# Group14ReceiverSchematic.net
KiCad netlist of a schematic drawn in Altium Designer
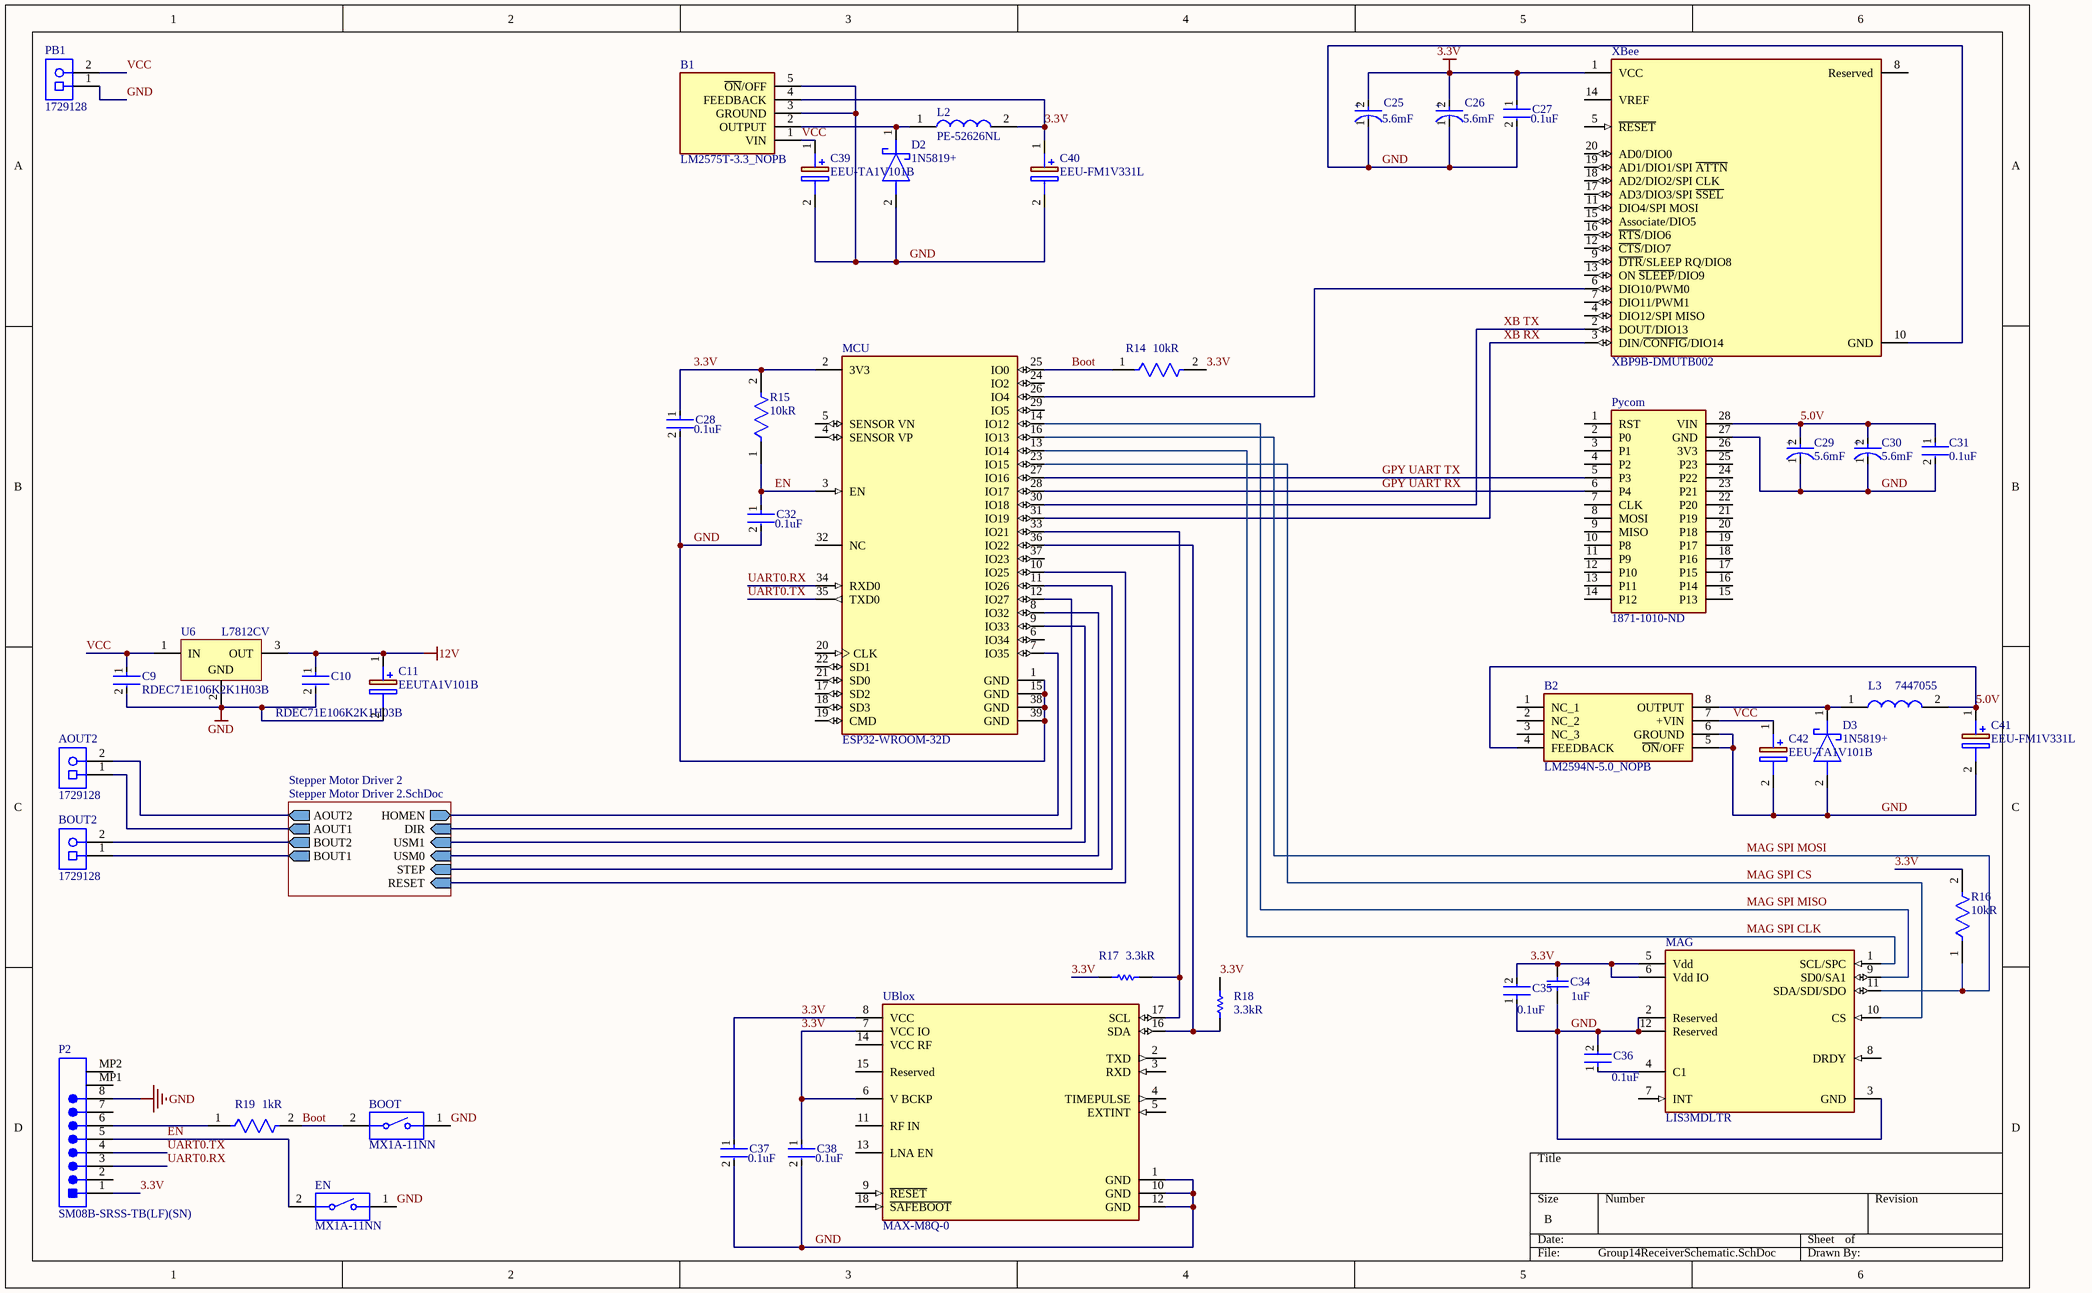
[diagram p0: Group14ReceiverSchematic.SchDoc]

(export (version "E")
  (design (tool "Eeschema 10.0.6"))
  (components
    (comp (ref "AOUT2")
      (value "1729128")
      (footprint "PHOE-1729128-2_V")
      (description "PCB Terminal Block, 13.5 A, 400 V, 2-Pin THD, RoHS, Bulk")
      (fields (field (name "MANUFACTURER") "Phoenix Contact"))
      (libsource (lib "Altium Content Vault") (part "CN-2P-F-R2"))
    )
    (comp (ref "B1")
      (value "LM2575T-3.3_NOPB")
      (footprint "SamacSys:LM2575T33NOPB")
      (description "Integrated Circuit")
      (fields
        (field (name "MANUFACTURER_PART_NUMBER") "LM2575T-3.3/NOPB")
        (field (name "MOUSER PART NUMBER") "926-LM2575T-33/NOPB")
      )
      (libsource (lib "SamacSys") (part "LM2575T-3.3_NOPB"))
    )
    (comp (ref "B2")
      (value "LM2594N-5.0_NOPB")
      (footprint "SamacSys:DIP794W53P254L959H508Q8N")
      (description "Integrated Circuit")
      (fields
        (field (name "MANUFACTURER_PART_NUMBER") "LM2594N-5.0/NOPB")
        (field (name "MOUSER PART NUMBER") "926-LM2594N-5.0/NOPB")
      )
      (libsource (lib "*") (part "LM2594N-5.0_NOPB"))
    )
    (comp (ref "BOOT")
      (value "MX1A-11NN")
      (footprint "CHRY-MX1A-11NN_V")
      (description "Keymodule MX, SPST, IP40, 12 V Max, 10 mA Max, -10 to 70 degC, 2-Pin THD, RoHS, Bulk")
      (fields (field (name "PART NO") "MX1A11NN") (field (name "MANUFACTURER") "Cherry"))
      (libsource (lib "Altium Content Vault") (part "KEYSW-SPST-2"))
    )
    (comp (ref "BOUT2")
      (value "1729128")
      (footprint "PHOE-1729128-2_V")
      (description "PCB Terminal Block, 13.5 A, 400 V, 2-Pin THD, RoHS, Bulk")
      (fields (field (name "MANUFACTURER") "Phoenix Contact"))
      (libsource (lib "Altium Content Vault") (part "CN-2P-F-R2"))
    )
    (comp (ref "C9")
      (value "RDEC71E106K2K1H03B")
      (footprint "FP-RDE2M1-MFG")
      (description "Ceramic Capacitor 10uF ±10% 25V X7S Radial")
      (fields (field (name "TOLERANCE") "10%"))
      (libsource (lib "Altium Content Vault") (part "b4654b650e69147ec39a6b967a45e02"))
    )
    (comp (ref "C10")
      (value "RDEC71E106K2K1H03B")
      (footprint "FP-RDE2M1-MFG")
      (description "Ceramic Capacitor 10uF ±10% 25V X7S Radial")
      (fields (field (name "TOLERANCE") "10%"))
      (libsource (lib "Altium Content Vault") (part "b4654b650e69147ec39a6b967a45e02"))
    )
    (comp (ref "C11")
      (value "EEUTA1V101B")
      (footprint "SamacSys:CAPPRD500W65D1000H1350")
      (description "Capacitor Polarised")
      (libsource (lib "*") (part "EEUTA1V101B"))
    )
    (comp (ref "C25")
      (value "EEUFM0J562S")
      (footprint "FP-RAD-TH-D_16_0_5-L_20_2-MFG")
      (description "Aluminum Electrolytic Capacitors (Radial Lead Type) 5600uF ±20% 6.3V")
      (fields
        (field (name "TOLERANCE") "20%")
        (field (name "VOLTAGE") "6.3V")
        (field (name "CAPACITANCE") "5.6mF")
      )
      (libsource (lib "Altium Content Vault") (part "203bc49f2ac43e59fd269a8c329ed05"))
    )
    (comp (ref "C26")
      (value "EEUFM0J562S")
      (footprint "FP-RAD-TH-D_16_0_5-L_20_2-MFG")
      (description "Aluminum Electrolytic Capacitors (Radial Lead Type) 5600uF ±20% 6.3V")
      (fields
        (field (name "TOLERANCE") "20%")
        (field (name "VOLTAGE") "6.3V")
        (field (name "CAPACITANCE") "5.6mF")
      )
      (libsource (lib "Altium Content Vault") (part "203bc49f2ac43e59fd269a8c329ed05"))
    )
    (comp (ref "C27")
      (value "RCER71E104K0K1H03B")
      (footprint "FP-RCE0K1-MFG")
      (description "Cap Ceramic 100nF 25V X7R ±10% Radial 5mm +125°C Automotive Bulk")
      (fields (field (name "CAPACITANCE") "0.1uF"))
      (libsource (lib "Altium Content Vault") (part "b4654b650e69147ec39a6b967a45e02"))
    )
    (comp (ref "C28")
      (value "RCER71E104K0K1H03B")
      (footprint "FP-RCE0K1-MFG")
      (description "Cap Ceramic 100nF 25V X7R ±10% Radial 5mm +125°C Automotive Bulk")
      (fields (field (name "CAPACITANCE") "0.1uF"))
      (libsource (lib "Altium Content Vault") (part "b4654b650e69147ec39a6b967a45e02"))
    )
    (comp (ref "C29")
      (value "EEUFM0J562S")
      (footprint "FP-RAD-TH-D_16_0_5-L_20_2-MFG")
      (description "Aluminum Electrolytic Capacitors (Radial Lead Type) 5600uF ±20% 6.3V")
      (fields
        (field (name "TOLERANCE") "20%")
        (field (name "VOLTAGE") "6.3V")
        (field (name "CAPACITANCE") "5.6mF")
      )
      (libsource (lib "Altium Content Vault") (part "203bc49f2ac43e59fd269a8c329ed05"))
    )
    (comp (ref "C30")
      (value "EEUFM0J562S")
      (footprint "FP-RAD-TH-D_16_0_5-L_20_2-MFG")
      (description "Aluminum Electrolytic Capacitors (Radial Lead Type) 5600uF ±20% 6.3V")
      (fields
        (field (name "TOLERANCE") "20%")
        (field (name "VOLTAGE") "6.3V")
        (field (name "CAPACITANCE") "5.6mF")
      )
      (libsource (lib "Altium Content Vault") (part "203bc49f2ac43e59fd269a8c329ed05"))
    )
    (comp (ref "C31")
      (value "RCER71E104K0K1H03B")
      (footprint "FP-RCE0K1-MFG")
      (description "Cap Ceramic 100nF 25V X7R ±10% Radial 5mm +125°C Automotive Bulk")
      (fields (field (name "CAPACITANCE") "0.1uF"))
      (libsource (lib "Altium Content Vault") (part "b4654b650e69147ec39a6b967a45e02"))
    )
    (comp (ref "C32")
      (value "RCER71E104K0K1H03B")
      (footprint "FP-RCE0K1-MFG")
      (description "Cap Ceramic 100nF 25V X7R ±10% Radial 5mm +125°C Automotive Bulk")
      (fields (field (name "CAPACITANCE") "0.1uF"))
      (libsource (lib "Altium Content Vault") (part "b4654b650e69147ec39a6b967a45e02"))
    )
    (comp (ref "C34")
      (value "0805YC105JAT2A")
      (footprint "CAPC2013X140X50ML20T25")
      (fields (field (name "MANUFACTURER") "AVX Interconnect / Elco") (field (name "CAPACITANCE") "1uF"))
      (libsource (lib "Altium Content Vault") (part "CAP"))
    )
    (comp (ref "C35")
      (value "RCER71E104K0K1H03B")
      (footprint "FP-RCE0K1-MFG")
      (description "Cap Ceramic 100nF 25V X7R ±10% Radial 5mm +125°C Automotive Bulk")
      (fields (field (name "CAPACITANCE") "0.1uF"))
      (libsource (lib "Altium Content Vault") (part "b4654b650e69147ec39a6b967a45e02"))
    )
    (comp (ref "C36")
      (value "RCER71E104K0K1H03B")
      (footprint "FP-RCE0K1-MFG")
      (description "Cap Ceramic 100nF 25V X7R ±10% Radial 5mm +125°C Automotive Bulk")
      (fields (field (name "CAPACITANCE") "0.1uF"))
      (libsource (lib "Altium Content Vault") (part "b4654b650e69147ec39a6b967a45e02"))
    )
    (comp (ref "C37")
      (value "RCER71E104K0K1H03B")
      (footprint "FP-RCE0K1-MFG")
      (description "Cap Ceramic 100nF 25V X7R ±10% Radial 5mm +125°C Automotive Bulk")
      (fields (field (name "CAPACITANCE") "0.1uF"))
      (libsource (lib "Altium Content Vault") (part "b4654b650e69147ec39a6b967a45e02"))
    )
    (comp (ref "C38")
      (value "RCER71E104K0K1H03B")
      (footprint "FP-RCE0K1-MFG")
      (description "Cap Ceramic 100nF 25V X7R ±10% Radial 5mm +125°C Automotive Bulk")
      (fields (field (name "CAPACITANCE") "0.1uF"))
      (libsource (lib "Altium Content Vault") (part "b4654b650e69147ec39a6b967a45e02"))
    )
    (comp (ref "C39")
      (value "EEU-TA1V101B")
      (footprint "SamacSys:CAPPRD500W65D1000H1350")
      (description "Capacitor Polarised")
      (fields (field (name "MOUSER PART NUMBER") "667-EEU-TA1V101B"))
      (libsource (lib "*") (part "EEU-TA1V101B"))
    )
    (comp (ref "C40")
      (value "EEU-FM1V331L")
      (footprint "SamacSys:CAPPRD350W60D800H2200")
      (description "Capacitor Polarised")
      (fields (field (name "MOUSER PART NUMBER") "667-EEU-FM1V331L"))
      (libsource (lib "*") (part "EEU-FM1V331L"))
    )
    (comp (ref "C41")
      (value "EEU-FM1V331L")
      (footprint "SamacSys:CAPPRD350W60D800H2200")
      (description "Capacitor Polarised")
      (fields (field (name "MOUSER PART NUMBER") "667-EEU-FM1V331L"))
      (libsource (lib "*") (part "EEU-FM1V331L"))
    )
    (comp (ref "C42")
      (value "EEU-TA1V101B")
      (footprint "SamacSys:CAPPRD500W65D1000H1350")
      (description "Capacitor Polarised")
      (fields (field (name "MOUSER PART NUMBER") "667-EEU-TA1V101B"))
      (libsource (lib "*") (part "EEU-TA1V101B"))
    )
    (comp (ref "D2")
      (value "1N5819+")
      (footprint "SamacSys:DIOAD1410W86L470D235")
      (description "Schottky Diode")
      (libsource (lib "SamacSys") (part "1N5819+"))
    )
    (comp (ref "D3")
      (value "1N5819+")
      (footprint "SamacSys:DIOAD1410W86L470D235")
      (description "Schottky Diode")
      (libsource (lib "SamacSys") (part "1N5819+"))
    )
    (comp (ref "EN")
      (value "MX1A-11NN")
      (footprint "CHRY-MX1A-11NN_V")
      (description "Keymodule MX, SPST, IP40, 12 V Max, 10 mA Max, -10 to 70 degC, 2-Pin THD, RoHS, Bulk")
      (fields (field (name "PART NO") "MX1A11NN") (field (name "MANUFACTURER") "Cherry"))
      (libsource (lib "Altium Content Vault") (part "KEYSW-SPST-2"))
    )
    (comp (ref "L2")
      (value "PE-52626NL")
      (footprint "SamacSys:PE52626NL")
      (description "Inductor")
      (fields (field (name "MOUSER PART NUMBER") "673-PE-52626NL"))
      (libsource (lib "SamacSys") (part "PE-52626NL"))
    )
    (comp (ref "L3")
      (value "7447055")
      (footprint "SamacSys:7447055")
      (description "Inductor")
      (fields (field (name "MOUSER PART NUMBER") "710-7447055"))
      (libsource (lib "*") (part "7447055"))
    )
    (comp (ref "MAG")
      (value "LIS3MDLTR")
      (footprint "FP-VFLGA-12-8365767-MFG")
      (description "SENSOR MR I2C/SPI 12LGA")
      (fields
        (field (name "OCTOPART") "https://octopart.com/lis3mdltr-stmicroelectronics-29403125")
        (field (name "MANUFACTURER") "STMicroelectronics")
      )
      (libsource (lib "Altium Content Vault") (part "41c0331d4207a07573b21020ef49d7d"))
    )
    (comp (ref "MCU")
      (value "ESP32-WROOM-32D")
      (footprint "FP-ESP32-WROOM-32D-MFG")
      (description "WIFI MODULE 32MBITS SPI FLASH")
      (fields
        (field (name "OCTOPART") "https://octopart.com/esp32-wroom-32d-espressif+systems-91040050")
        (field (name "MANUFACTURER") "Espressif Systems")
      )
      (libsource (lib "Altium Content Vault") (part "a031a76f8c27026a7a7f4657ff233a3"))
    )
    (comp (ref "P2")
      (value "SM08B-SRSS-TB(LF)(SN)")
      (footprint "JST-SM08B-SRSS-TB_V")
      (description "Male Header, Pitch 1 mm, 1 x 8 Position, Height 2.95 mm, -25 to 85 degC, RoHS, Tape and Reel")
      (fields (field (name "MANUFACTURER") "JST"))
      (libsource (lib "Altium Content Vault") (part "CN-1P-2M-R8"))
    )
    (comp (ref "PB1")
      (value "1729128")
      (footprint "PHOE-1729128-2_V")
      (description "PCB Terminal Block, 13.5 A, 400 V, 2-Pin THD, RoHS, Bulk")
      (fields (field (name "MANUFACTURER") "Phoenix Contact"))
      (libsource (lib "Altium Content Vault") (part "CN-2P-F-R2"))
    )
    (comp (ref "Pycom")
      (value "1871-1010-ND")
      (footprint "SamacSys:18711010ND")
      (description "Integrated Circuit")
      (libsource (lib "*") (part "1871-1010-ND"))
    )
    (comp (ref "R14")
      (value "CR0805-FX-1002ELF")
      (footprint "FP-CR0805-IPC_A")
      (description "Thick Film Chip Resistors 0805 10kΩ 0.125W 1% 100ppm/°C")
      (fields (field (name "TOLERANCE") "1%") (field (name "RESISTANCE") "10kR"))
      (libsource (lib "Altium Content Vault") (part "1029c3af85768c4190bb7ad29bc67b5"))
    )
    (comp (ref "R15")
      (value "CR0805-FX-1002ELF")
      (footprint "FP-CR0805-IPC_A")
      (description "Thick Film Chip Resistors 0805 10kΩ 0.125W 1% 100ppm/°C")
      (fields (field (name "TOLERANCE") "1%") (field (name "RESISTANCE") "10kR"))
      (libsource (lib "Altium Content Vault") (part "1029c3af85768c4190bb7ad29bc67b5"))
    )
    (comp (ref "R16")
      (value "CR0805-FX-1002ELF")
      (footprint "FP-CR0805-IPC_A")
      (description "Thick Film Chip Resistors 0805 10kΩ 0.125W 1% 100ppm/°C")
      (fields (field (name "TOLERANCE") "1%") (field (name "RESISTANCE") "10kR"))
      (libsource (lib "Altium Content Vault") (part "1029c3af85768c4190bb7ad29bc67b5"))
    )
    (comp (ref "R17")
      (value "RK73H1JTTD3301F")
      (footprint "RESC1608X55X30NL20T10")
      (fields (field (name "MANUFACTURER") "KOA Speer") (field (name "RESISTANCE") "3.3kR"))
      (libsource (lib "Altium Content Vault") (part "RES"))
    )
    (comp (ref "R18")
      (value "RK73H1JTTD3301F")
      (footprint "RESC1608X55X30NL20T10")
      (fields (field (name "MANUFACTURER") "KOA Speer") (field (name "RESISTANCE") "3.3kR"))
      (libsource (lib "Altium Content Vault") (part "RES"))
    )
    (comp (ref "R19")
      (value "1kR")
      (footprint "FP-RN732A-MFG")
      (description "SMD Chip Resistor, Thin Film, 1.0KΩ, 100 V, 0805 [2012 Metric], 100 mW, 0.1%, RN73 Series")
      (fields (field (name "TOLERANCE") "0.1%") (field (name "MANUFACTURER PART NUMBER") "RN73C2A1K0B"))
      (libsource (lib "Altium Content Vault") (part "1029c3af85768c4190bb7ad29bc67b5"))
    )
    (comp (ref "U6")
      (value "L7812CV")
      (footprint "TO220")
      (description "Positive Voltage Regulator, 12V, 3-Pin TO-220")
      (libsource (lib "Altium Content Vault") (part "PM-REG-L4940-SIL3"))
    )
    (comp (ref "UBlox")
      (value "MAX-M8Q-0")
      (footprint "FP-MAX-M8Q-0-MFG")
      (description "RF RCVR GNSS/GPS 1.575GHZ 18LCC")
      (libsource (lib "Altium Content Vault") (part "3a4eaf80b39255b10f8ea21395ff7da"))
    )
    (comp (ref "XBee")
      (value "XBP9B-DMUTB002")
      (footprint "FP-XBP9B-DMUTB002-MFG")
      (description "RX TXRX MOD ISM < 1GHZ U.FL TH")
      (libsource (lib "Altium Content Vault") (part "053d8e65a610ce00d52093c0e212ca3"))
    )
  )
  (nets
    (net (code "1") (name "/5.0V") (class "Default")
      (node (ref "B2") (pin "4") (pinfunction "FEEDBACK_4") (pintype "passive"))
      (node (ref "C29") (pin "2") (pinfunction "A_2") (pintype "passive"))
      (node (ref "C30") (pin "2") (pinfunction "A_2") (pintype "passive"))
      (node (ref "C31") (pin "1") (pinfunction "1_1") (pintype "passive"))
      (node (ref "C41") (pin "1") (pinfunction "+_1") (pintype "passive"))
      (node (ref "L3") (pin "2") (pinfunction "2_2") (pintype "passive"))
      (node (ref "Pycom") (pin "28") (pinfunction "VIN_28") (pintype "passive"))
    )
    (net (code "2") (name "/AOUT1") (class "Default")
      (node (ref "AOUT2") (pin "1") (pinfunction "1_1") (pintype "passive"))
    )
    (net (code "3") (name "/AOUT2") (class "Default")
      (node (ref "AOUT2") (pin "2") (pinfunction "2_2") (pintype "passive"))
    )
    (net (code "4") (name "/BOUT1") (class "Default")
      (node (ref "BOUT2") (pin "1") (pinfunction "1_1") (pintype "passive"))
    )
    (net (code "5") (name "/BOUT2") (class "Default")
      (node (ref "BOUT2") (pin "2") (pinfunction "2_2") (pintype "passive"))
    )
    (net (code "6") (name "/Boot") (class "Default")
      (node (ref "BOOT") (pin "2") (pinfunction "2_2") (pintype "passive"))
      (node (ref "MCU") (pin "25") (pinfunction "IO0_25") (pintype "bidirectional"))
      (node (ref "R14") (pin "1") (pinfunction "1_1") (pintype "passive"))
      (node (ref "R19") (pin "2") (pinfunction "2_2") (pintype "passive"))
    )
    (net (code "7") (name "/DIR") (class "Default")
      (node (ref "MCU") (pin "12") (pinfunction "IO27_12") (pintype "bidirectional"))
    )
    (net (code "8") (name "/EN") (class "Default")
      (node (ref "C32") (pin "1") (pinfunction "1_1") (pintype "passive"))
      (node (ref "EN") (pin "2") (pinfunction "2_2") (pintype "passive"))
      (node (ref "MCU") (pin "3") (pinfunction "EN_3") (pintype "input"))
      (node (ref "P2") (pin "5") (pinfunction "5_5") (pintype "passive"))
      (node (ref "R15") (pin "1") (pinfunction "1_1") (pintype "passive"))
    )
    (net (code "9") (name "/GPY UART RX") (class "Default")
      (node (ref "MCU") (pin "28") (pinfunction "IO17_28") (pintype "bidirectional"))
      (node (ref "Pycom") (pin "6") (pinfunction "P4_6") (pintype "passive"))
    )
    (net (code "10") (name "/GPY UART TX") (class "Default")
      (node (ref "MCU") (pin "27") (pinfunction "IO16_27") (pintype "bidirectional"))
      (node (ref "Pycom") (pin "5") (pinfunction "P3_5") (pintype "passive"))
    )
    (net (code "11") (name "/HOMEN") (class "Default")
      (node (ref "MCU") (pin "7") (pinfunction "IO35_7") (pintype "bidirectional"))
    )
    (net (code "12") (name "/MAG SPI CLK") (class "Default")
      (node (ref "MAG") (pin "1") (pinfunction "SCL/SPC_1") (pintype "input"))
      (node (ref "MCU") (pin "13") (pinfunction "IO14_13") (pintype "bidirectional"))
    )
    (net (code "13") (name "/MAG SPI CS") (class "Default")
      (node (ref "MAG") (pin "10") (pinfunction "CS_10") (pintype "input"))
      (node (ref "MCU") (pin "23") (pinfunction "IO15_23") (pintype "bidirectional"))
    )
    (net (code "14") (name "/MAG SPI MISO") (class "Default")
      (node (ref "MAG") (pin "9") (pinfunction "SD0/SA1_9") (pintype "bidirectional"))
      (node (ref "MCU") (pin "14") (pinfunction "IO12_14") (pintype "bidirectional"))
    )
    (net (code "15") (name "/MAG SPI MOSI") (class "Default")
      (node (ref "MAG") (pin "11") (pinfunction "SDA/SDI/SDO_11") (pintype "bidirectional"))
      (node (ref "MCU") (pin "16") (pinfunction "IO13_16") (pintype "bidirectional"))
      (node (ref "R16") (pin "1") (pinfunction "1_1") (pintype "passive"))
    )
    (net (code "16") (name "/RESET") (class "Default")
      (node (ref "MCU") (pin "10") (pinfunction "IO25_10") (pintype "bidirectional"))
    )
    (net (code "17") (name "/STEP") (class "Default")
      (node (ref "MCU") (pin "11") (pinfunction "IO26_11") (pintype "bidirectional"))
    )
    (net (code "18") (name "/UART0.RX") (class "Default")
      (node (ref "MCU") (pin "34") (pinfunction "RXD0_34") (pintype "input"))
      (node (ref "P2") (pin "3") (pinfunction "3_3") (pintype "passive"))
    )
    (net (code "19") (name "/UART0.TX") (class "Default")
      (node (ref "MCU") (pin "35") (pinfunction "TXD0_35") (pintype "output"))
      (node (ref "P2") (pin "4") (pinfunction "4_4") (pintype "passive"))
    )
    (net (code "20") (name "/USM0") (class "Default")
      (node (ref "MCU") (pin "8") (pinfunction "IO32_8") (pintype "bidirectional"))
    )
    (net (code "21") (name "/USM1") (class "Default")
      (node (ref "MCU") (pin "9") (pinfunction "IO33_9") (pintype "bidirectional"))
    )
    (net (code "22") (name "/VCC") (class "Default")
      (node (ref "B1") (pin "1") (pinfunction "VIN_1") (pintype "passive"))
      (node (ref "B2") (pin "7") (pinfunction "+VIN_7") (pintype "passive"))
      (node (ref "C39") (pin "1") (pinfunction "+_1") (pintype "passive"))
      (node (ref "C42") (pin "1") (pinfunction "+_1") (pintype "passive"))
      (node (ref "C9") (pin "1") (pinfunction "1_1") (pintype "passive"))
      (node (ref "PB1") (pin "2") (pinfunction "2_2") (pintype "passive"))
      (node (ref "U6") (pin "1") (pinfunction "IN_1") (pintype "power_in"))
    )
    (net (code "23") (name "/XB RX") (class "Default")
      (node (ref "MCU") (pin "31") (pinfunction "IO19_31") (pintype "bidirectional"))
      (node (ref "XBee") (pin "3") (pinfunction "DIN/~{CONFIG}/DIO14_3") (pintype "bidirectional"))
    )
    (net (code "24") (name "/XB TX") (class "Default")
      (node (ref "MCU") (pin "30") (pinfunction "IO18_30") (pintype "bidirectional"))
      (node (ref "XBee") (pin "2") (pinfunction "DOUT/DIO13_2") (pintype "bidirectional"))
    )
    (net (code "25") (name "3.3V") (class "Default")
      (node (ref "B1") (pin "4") (pinfunction "FEEDBACK_4") (pintype "passive"))
      (node (ref "C25") (pin "2") (pinfunction "A_2") (pintype "passive"))
      (node (ref "C26") (pin "2") (pinfunction "A_2") (pintype "passive"))
      (node (ref "C27") (pin "1") (pinfunction "1_1") (pintype "passive"))
      (node (ref "C28") (pin "1") (pinfunction "1_1") (pintype "passive"))
      (node (ref "C34") (pin "2") (pinfunction "2_2") (pintype "passive"))
      (node (ref "C35") (pin "2") (pinfunction "2_2") (pintype "passive"))
      (node (ref "C37") (pin "1") (pinfunction "1_1") (pintype "passive"))
      (node (ref "C38") (pin "1") (pinfunction "1_1") (pintype "passive"))
      (node (ref "C40") (pin "1") (pinfunction "+_1") (pintype "passive"))
      (node (ref "L2") (pin "2") (pinfunction "2_2") (pintype "passive"))
      (node (ref "MAG") (pin "5") (pinfunction "Vdd_5") (pintype "power_in"))
      (node (ref "MAG") (pin "6") (pinfunction "Vdd_IO_6") (pintype "power_in"))
      (node (ref "MCU") (pin "2") (pinfunction "3V3_2") (pintype "power_in"))
      (node (ref "P2") (pin "1") (pinfunction "1_1") (pintype "passive"))
      (node (ref "R14") (pin "2") (pinfunction "2_2") (pintype "passive"))
      (node (ref "R15") (pin "2") (pinfunction "2_2") (pintype "passive"))
      (node (ref "R16") (pin "2") (pinfunction "2_2") (pintype "passive"))
      (node (ref "R17") (pin "2") (pinfunction "2_2") (pintype "passive"))
      (node (ref "R18") (pin "2") (pinfunction "2_2") (pintype "passive"))
      (node (ref "UBlox") (pin "6") (pinfunction "V_BCKP_6") (pintype "power_in"))
      (node (ref "UBlox") (pin "7") (pinfunction "VCC_IO_7") (pintype "power_in"))
      (node (ref "UBlox") (pin "8") (pinfunction "VCC_8") (pintype "power_in"))
      (node (ref "XBee") (pin "1") (pinfunction "VCC_1") (pintype "power_in"))
    )
    (net (code "26") (name "12V") (class "Default")
      (node (ref "C10") (pin "1") (pinfunction "1_1") (pintype "passive"))
      (node (ref "C11") (pin "1") (pinfunction "+_1") (pintype "passive"))
      (node (ref "U6") (pin "3") (pinfunction "OUT_3") (pintype "power_in"))
    )
    (net (code "27") (name "GND") (class "Default")
      (node (ref "B1") (pin "3") (pinfunction "GROUND_3") (pintype "passive"))
      (node (ref "B1") (pin "5") (pinfunction "~{ON}/OFF_5") (pintype "passive"))
      (node (ref "B2") (pin "5") (pinfunction "~{ON}/OFF_5") (pintype "passive"))
      (node (ref "B2") (pin "6") (pinfunction "GROUND_6") (pintype "passive"))
      (node (ref "BOOT") (pin "1") (pinfunction "1_1") (pintype "passive"))
      (node (ref "C10") (pin "2") (pinfunction "2_2") (pintype "passive"))
      (node (ref "C11") (pin "2") (pinfunction "-_2") (pintype "passive"))
      (node (ref "C25") (pin "1") (pinfunction "C_1") (pintype "passive"))
      (node (ref "C26") (pin "1") (pinfunction "C_1") (pintype "passive"))
      (node (ref "C27") (pin "2") (pinfunction "2_2") (pintype "passive"))
      (node (ref "C28") (pin "2") (pinfunction "2_2") (pintype "passive"))
      (node (ref "C29") (pin "1") (pinfunction "C_1") (pintype "passive"))
      (node (ref "C30") (pin "1") (pinfunction "C_1") (pintype "passive"))
      (node (ref "C31") (pin "2") (pinfunction "2_2") (pintype "passive"))
      (node (ref "C32") (pin "2") (pinfunction "2_2") (pintype "passive"))
      (node (ref "C34") (pin "1") (pinfunction "1_1") (pintype "passive"))
      (node (ref "C35") (pin "1") (pinfunction "1_1") (pintype "passive"))
      (node (ref "C36") (pin "2") (pinfunction "2_2") (pintype "passive"))
      (node (ref "C37") (pin "2") (pinfunction "2_2") (pintype "passive"))
      (node (ref "C38") (pin "2") (pinfunction "2_2") (pintype "passive"))
      (node (ref "C39") (pin "2") (pinfunction "-_2") (pintype "passive"))
      (node (ref "C40") (pin "2") (pinfunction "-_2") (pintype "passive"))
      (node (ref "C41") (pin "2") (pinfunction "-_2") (pintype "passive"))
      (node (ref "C42") (pin "2") (pinfunction "-_2") (pintype "passive"))
      (node (ref "C9") (pin "2") (pinfunction "2_2") (pintype "passive"))
      (node (ref "D2") (pin "2") (pinfunction "A_2") (pintype "passive"))
      (node (ref "D3") (pin "2") (pinfunction "A_2") (pintype "passive"))
      (node (ref "EN") (pin "1") (pinfunction "1_1") (pintype "passive"))
      (node (ref "MAG") (pin "12") (pinfunction "Reserved_12") (pintype "passive"))
      (node (ref "MAG") (pin "2") (pinfunction "Reserved_2") (pintype "passive"))
      (node (ref "MAG") (pin "3") (pinfunction "GND_3") (pintype "power_in"))
      (node (ref "MCU") (pin "1") (pinfunction "GND_1") (pintype "power_in"))
      (node (ref "MCU") (pin "15") (pinfunction "GND_15") (pintype "power_in"))
      (node (ref "MCU") (pin "38") (pinfunction "GND_38") (pintype "power_in"))
      (node (ref "MCU") (pin "39") (pinfunction "GND_39") (pintype "power_in"))
      (node (ref "P2") (pin "8") (pinfunction "8_8") (pintype "passive"))
      (node (ref "PB1") (pin "1") (pinfunction "1_1") (pintype "passive"))
      (node (ref "Pycom") (pin "27") (pinfunction "GND_27") (pintype "passive"))
      (node (ref "U6") (pin "2") (pinfunction "GND_2") (pintype "power_in"))
      (node (ref "UBlox") (pin "1") (pinfunction "GND_1") (pintype "power_in"))
      (node (ref "UBlox") (pin "10") (pinfunction "GND_10") (pintype "power_in"))
      (node (ref "UBlox") (pin "12") (pinfunction "GND_12") (pintype "power_in"))
      (node (ref "XBee") (pin "10") (pinfunction "GND_10") (pintype "power_in"))
    )
    (net (code "28") (name "Net-(B1-OUTPUT)") (class "Default")
      (node (ref "B1") (pin "2") (pinfunction "OUTPUT_2") (pintype "passive"))
      (node (ref "D2") (pin "1") (pinfunction "K_1") (pintype "passive"))
      (node (ref "L2") (pin "1") (pinfunction "1_1") (pintype "passive"))
    )
    (net (code "29") (name "Net-(B2-OUTPUT)") (class "Default")
      (node (ref "B2") (pin "8") (pinfunction "OUTPUT_8") (pintype "passive"))
      (node (ref "D3") (pin "1") (pinfunction "K_1") (pintype "passive"))
      (node (ref "L3") (pin "1") (pinfunction "1_1") (pintype "passive"))
    )
    (net (code "30") (name "Net-(MAG-C1)") (class "Default")
      (node (ref "C36") (pin "1") (pinfunction "1_1") (pintype "passive"))
      (node (ref "MAG") (pin "4") (pinfunction "C1_4") (pintype "passive"))
    )
    (net (code "31") (name "Net-(MCU-IO4)") (class "Default")
      (node (ref "MCU") (pin "26") (pinfunction "IO4_26") (pintype "bidirectional"))
      (node (ref "XBee") (pin "6") (pinfunction "DIO10/PWM0_6") (pintype "bidirectional"))
    )
    (net (code "32") (name "Net-(MCU-IO21)") (class "Default")
      (node (ref "MCU") (pin "33") (pinfunction "IO21_33") (pintype "bidirectional"))
      (node (ref "R17") (pin "1") (pinfunction "1_1") (pintype "passive"))
      (node (ref "UBlox") (pin "17") (pinfunction "SCL_17") (pintype "bidirectional"))
    )
    (net (code "33") (name "Net-(MCU-IO22)") (class "Default")
      (node (ref "MCU") (pin "36") (pinfunction "IO22_36") (pintype "bidirectional"))
      (node (ref "R18") (pin "1") (pinfunction "1_1") (pintype "passive"))
      (node (ref "UBlox") (pin "16") (pinfunction "SDA_16") (pintype "bidirectional"))
    )
    (net (code "34") (name "Net-(P2-Pad6)") (class "Default")
      (node (ref "P2") (pin "6") (pinfunction "6_6") (pintype "passive"))
      (node (ref "R19") (pin "1") (pinfunction "1_1") (pintype "passive"))
    )
    (net (code "35") (name "unconnected-(B2-NC_1-Pad1)") (class "Default")
      (node (ref "B2") (pin "1") (pinfunction "NC_1_1") (pintype "passive"))
    )
    (net (code "36") (name "unconnected-(B2-NC_2-Pad2)") (class "Default")
      (node (ref "B2") (pin "2") (pinfunction "NC_2_2") (pintype "passive"))
    )
    (net (code "37") (name "unconnected-(B2-NC_3-Pad3)") (class "Default")
      (node (ref "B2") (pin "3") (pinfunction "NC_3_3") (pintype "passive"))
    )
    (net (code "38") (name "unconnected-(MAG-DRDY-Pad8)") (class "Default")
      (node (ref "MAG") (pin "8") (pinfunction "DRDY_8") (pintype "input"))
    )
    (net (code "39") (name "unconnected-(MAG-INT-Pad7)") (class "Default")
      (node (ref "MAG") (pin "7") (pinfunction "INT_7") (pintype "input"))
    )
    (net (code "40") (name "unconnected-(MCU-CLK-Pad20)") (class "Default")
      (node (ref "MCU") (pin "20") (pinfunction "CLK_20") (pintype "input"))
    )
    (net (code "41") (name "unconnected-(MCU-CMD-Pad19)") (class "Default")
      (node (ref "MCU") (pin "19") (pinfunction "CMD_19") (pintype "bidirectional"))
    )
    (net (code "42") (name "unconnected-(MCU-IO2-Pad24)") (class "Default")
      (node (ref "MCU") (pin "24") (pinfunction "IO2_24") (pintype "bidirectional"))
    )
    (net (code "43") (name "unconnected-(MCU-IO5-Pad29)") (class "Default")
      (node (ref "MCU") (pin "29") (pinfunction "IO5_29") (pintype "bidirectional"))
    )
    (net (code "44") (name "unconnected-(MCU-IO23-Pad37)") (class "Default")
      (node (ref "MCU") (pin "37") (pinfunction "IO23_37") (pintype "bidirectional"))
    )
    (net (code "45") (name "unconnected-(MCU-IO34-Pad6)") (class "Default")
      (node (ref "MCU") (pin "6") (pinfunction "IO34_6") (pintype "bidirectional"))
    )
    (net (code "46") (name "unconnected-(MCU-NC-Pad32)") (class "Default")
      (node (ref "MCU") (pin "32") (pinfunction "NC_32") (pintype "passive"))
    )
    (net (code "47") (name "unconnected-(MCU-SD0-Pad21)") (class "Default")
      (node (ref "MCU") (pin "21") (pinfunction "SD0_21") (pintype "bidirectional"))
    )
    (net (code "48") (name "unconnected-(MCU-SD1-Pad22)") (class "Default")
      (node (ref "MCU") (pin "22") (pinfunction "SD1_22") (pintype "bidirectional"))
    )
    (net (code "49") (name "unconnected-(MCU-SD2-Pad17)") (class "Default")
      (node (ref "MCU") (pin "17") (pinfunction "SD2_17") (pintype "bidirectional"))
    )
    (net (code "50") (name "unconnected-(MCU-SD3-Pad18)") (class "Default")
      (node (ref "MCU") (pin "18") (pinfunction "SD3_18") (pintype "bidirectional"))
    )
    (net (code "51") (name "unconnected-(MCU-SENSOR_VN-Pad5)") (class "Default")
      (node (ref "MCU") (pin "5") (pinfunction "SENSOR_VN_5") (pintype "bidirectional"))
    )
    (net (code "52") (name "unconnected-(MCU-SENSOR_VP-Pad4)") (class "Default")
      (node (ref "MCU") (pin "4") (pinfunction "SENSOR_VP_4") (pintype "bidirectional"))
    )
    (net (code "53") (name "unconnected-(P2-Pad2)") (class "Default")
      (node (ref "P2") (pin "2") (pinfunction "2_2") (pintype "passive"))
    )
    (net (code "54") (name "unconnected-(P2-Pad7)") (class "Default")
      (node (ref "P2") (pin "7") (pinfunction "7_7") (pintype "passive"))
    )
    (net (code "55") (name "unconnected-(P2-PadMP1)") (class "Default")
      (node (ref "P2") (pin "MP1") (pinfunction "MP1_MP1") (pintype "passive"))
    )
    (net (code "56") (name "unconnected-(P2-PadMP2)") (class "Default")
      (node (ref "P2") (pin "MP2") (pinfunction "MP2_MP2") (pintype "passive"))
    )
    (net (code "57") (name "unconnected-(Pycom-3V3-Pad26)") (class "Default")
      (node (ref "Pycom") (pin "26") (pinfunction "3V3_26") (pintype "passive"))
    )
    (net (code "58") (name "unconnected-(Pycom-CLK-Pad7)") (class "Default")
      (node (ref "Pycom") (pin "7") (pinfunction "CLK_7") (pintype "passive"))
    )
    (net (code "59") (name "unconnected-(Pycom-MISO-Pad9)") (class "Default")
      (node (ref "Pycom") (pin "9") (pinfunction "MISO_9") (pintype "passive"))
    )
    (net (code "60") (name "unconnected-(Pycom-MOSI-Pad8)") (class "Default")
      (node (ref "Pycom") (pin "8") (pinfunction "MOSI_8") (pintype "passive"))
    )
    (net (code "61") (name "unconnected-(Pycom-P0-Pad2)") (class "Default")
      (node (ref "Pycom") (pin "2") (pinfunction "P0_2") (pintype "passive"))
    )
    (net (code "62") (name "unconnected-(Pycom-P1-Pad3)") (class "Default")
      (node (ref "Pycom") (pin "3") (pinfunction "P1_3") (pintype "passive"))
    )
    (net (code "63") (name "unconnected-(Pycom-P2-Pad4)") (class "Default")
      (node (ref "Pycom") (pin "4") (pinfunction "P2_4") (pintype "passive"))
    )
    (net (code "64") (name "unconnected-(Pycom-P8-Pad10)") (class "Default")
      (node (ref "Pycom") (pin "10") (pinfunction "P8_10") (pintype "passive"))
    )
    (net (code "65") (name "unconnected-(Pycom-P9-Pad11)") (class "Default")
      (node (ref "Pycom") (pin "11") (pinfunction "P9_11") (pintype "passive"))
    )
    (net (code "66") (name "unconnected-(Pycom-P10-Pad12)") (class "Default")
      (node (ref "Pycom") (pin "12") (pinfunction "P10_12") (pintype "passive"))
    )
    (net (code "67") (name "unconnected-(Pycom-P11-Pad13)") (class "Default")
      (node (ref "Pycom") (pin "13") (pinfunction "P11_13") (pintype "passive"))
    )
    (net (code "68") (name "unconnected-(Pycom-P12-Pad14)") (class "Default")
      (node (ref "Pycom") (pin "14") (pinfunction "P12_14") (pintype "passive"))
    )
    (net (code "69") (name "unconnected-(Pycom-P13-Pad15)") (class "Default")
      (node (ref "Pycom") (pin "15") (pinfunction "P13_15") (pintype "passive"))
    )
    (net (code "70") (name "unconnected-(Pycom-P14-Pad16)") (class "Default")
      (node (ref "Pycom") (pin "16") (pinfunction "P14_16") (pintype "passive"))
    )
    (net (code "71") (name "unconnected-(Pycom-P15-Pad17)") (class "Default")
      (node (ref "Pycom") (pin "17") (pinfunction "P15_17") (pintype "passive"))
    )
    (net (code "72") (name "unconnected-(Pycom-P16-Pad18)") (class "Default")
      (node (ref "Pycom") (pin "18") (pinfunction "P16_18") (pintype "passive"))
    )
    (net (code "73") (name "unconnected-(Pycom-P17-Pad19)") (class "Default")
      (node (ref "Pycom") (pin "19") (pinfunction "P17_19") (pintype "passive"))
    )
    (net (code "74") (name "unconnected-(Pycom-P18-Pad20)") (class "Default")
      (node (ref "Pycom") (pin "20") (pinfunction "P18_20") (pintype "passive"))
    )
    (net (code "75") (name "unconnected-(Pycom-P19-Pad21)") (class "Default")
      (node (ref "Pycom") (pin "21") (pinfunction "P19_21") (pintype "passive"))
    )
    (net (code "76") (name "unconnected-(Pycom-P20-Pad22)") (class "Default")
      (node (ref "Pycom") (pin "22") (pinfunction "P20_22") (pintype "passive"))
    )
    (net (code "77") (name "unconnected-(Pycom-P21-Pad23)") (class "Default")
      (node (ref "Pycom") (pin "23") (pinfunction "P21_23") (pintype "passive"))
    )
    (net (code "78") (name "unconnected-(Pycom-P22-Pad24)") (class "Default")
      (node (ref "Pycom") (pin "24") (pinfunction "P22_24") (pintype "passive"))
    )
    (net (code "79") (name "unconnected-(Pycom-P23-Pad25)") (class "Default")
      (node (ref "Pycom") (pin "25") (pinfunction "P23_25") (pintype "passive"))
    )
    (net (code "80") (name "unconnected-(Pycom-RST-Pad1)") (class "Default")
      (node (ref "Pycom") (pin "1") (pinfunction "RST_1") (pintype "passive"))
    )
    (net (code "81") (name "unconnected-(UBlox-EXTINT-Pad5)") (class "Default")
      (node (ref "UBlox") (pin "5") (pinfunction "EXTINT_5") (pintype "input"))
    )
    (net (code "82") (name "unconnected-(UBlox-LNA_EN-Pad13)") (class "Default")
      (node (ref "UBlox") (pin "13") (pinfunction "LNA_EN_13") (pintype "passive"))
    )
    (net (code "83") (name "unconnected-(UBlox-RF_IN-Pad11)") (class "Default")
      (node (ref "UBlox") (pin "11") (pinfunction "RF_IN_11") (pintype "passive"))
    )
    (net (code "84") (name "unconnected-(UBlox-RXD-Pad3)") (class "Default")
      (node (ref "UBlox") (pin "3") (pinfunction "RXD_3") (pintype "input"))
    )
    (net (code "85") (name "unconnected-(UBlox-Reserved-Pad15)") (class "Default")
      (node (ref "UBlox") (pin "15") (pinfunction "Reserved_15") (pintype "passive"))
    )
    (net (code "86") (name "unconnected-(UBlox-TIMEPULSE-Pad4)") (class "Default")
      (node (ref "UBlox") (pin "4") (pinfunction "TIMEPULSE_4") (pintype "output"))
    )
    (net (code "87") (name "unconnected-(UBlox-TXD-Pad2)") (class "Default")
      (node (ref "UBlox") (pin "2") (pinfunction "TXD_2") (pintype "output"))
    )
    (net (code "88") (name "unconnected-(UBlox-VCC_RF-Pad14)") (class "Default")
      (node (ref "UBlox") (pin "14") (pinfunction "VCC_RF_14") (pintype "power_in"))
    )
    (net (code "89") (name "unconnected-(UBlox-~{RESET}-Pad9)") (class "Default")
      (node (ref "UBlox") (pin "9") (pinfunction "~{RESET}_9") (pintype "input"))
    )
    (net (code "90") (name "unconnected-(UBlox-~{SAFEBOOT}-Pad18)") (class "Default")
      (node (ref "UBlox") (pin "18") (pinfunction "~{SAFEBOOT}_18") (pintype "input"))
    )
    (net (code "91") (name "unconnected-(XBee-AD0{slash}DIO0-Pad20)") (class "Default")
      (node (ref "XBee") (pin "20") (pinfunction "AD0/DIO0_20") (pintype "bidirectional"))
    )
    (net (code "92") (name "unconnected-(XBee-AD1{slash}DIO1{slash}SPI_~{ATTN}-Pad19)") (class "Default")
      (node (ref "XBee") (pin "19") (pinfunction "AD1/DIO1/SPI_~{ATTN}_19") (pintype "bidirectional"))
    )
    (net (code "93") (name "unconnected-(XBee-AD2{slash}DIO2{slash}SPI_CLK-Pad18)") (class "Default")
      (node (ref "XBee") (pin "18") (pinfunction "AD2/DIO2/SPI_CLK_18") (pintype "bidirectional"))
    )
    (net (code "94") (name "unconnected-(XBee-AD3{slash}DIO3{slash}SPI_~{SSEL}-Pad17)") (class "Default")
      (node (ref "XBee") (pin "17") (pinfunction "AD3/DIO3/SPI_~{SSEL}_17") (pintype "bidirectional"))
    )
    (net (code "95") (name "unconnected-(XBee-Associate{slash}DIO5-Pad15)") (class "Default")
      (node (ref "XBee") (pin "15") (pinfunction "Associate/DIO5_15") (pintype "bidirectional"))
    )
    (net (code "96") (name "unconnected-(XBee-DIO4{slash}SPI_MOSI-Pad11)") (class "Default")
      (node (ref "XBee") (pin "11") (pinfunction "DIO4/SPI_MOSI_11") (pintype "bidirectional"))
    )
    (net (code "97") (name "unconnected-(XBee-DIO11{slash}PWM1-Pad7)") (class "Default")
      (node (ref "XBee") (pin "7") (pinfunction "DIO11/PWM1_7") (pintype "bidirectional"))
    )
    (net (code "98") (name "unconnected-(XBee-DIO12{slash}SPI_MISO-Pad4)") (class "Default")
      (node (ref "XBee") (pin "4") (pinfunction "DIO12/SPI_MISO_4") (pintype "bidirectional"))
    )
    (net (code "99") (name "unconnected-(XBee-ON_~{SLEEP}{slash}DIO9-Pad13)") (class "Default")
      (node (ref "XBee") (pin "13") (pinfunction "ON_~{SLEEP}/DIO9_13") (pintype "bidirectional"))
    )
    (net (code "100") (name "unconnected-(XBee-Reserved-Pad8)") (class "Default")
      (node (ref "XBee") (pin "8") (pinfunction "Reserved_8") (pintype "passive"))
    )
    (net (code "101") (name "unconnected-(XBee-VREF-Pad14)") (class "Default")
      (node (ref "XBee") (pin "14") (pinfunction "VREF_14") (pintype "passive"))
    )
    (net (code "102") (name "unconnected-(XBee-~{CTS}{slash}DIO7-Pad12)") (class "Default")
      (node (ref "XBee") (pin "12") (pinfunction "~{CTS}/DIO7_12") (pintype "bidirectional"))
    )
    (net (code "103") (name "unconnected-(XBee-~{DTR}{slash}SLEEP_RQ{slash}DIO8-Pad9)") (class "Default")
      (node (ref "XBee") (pin "9") (pinfunction "~{DTR}/SLEEP_RQ/DIO8_9") (pintype "bidirectional"))
    )
    (net (code "104") (name "unconnected-(XBee-~{RESET}-Pad5)") (class "Default")
      (node (ref "XBee") (pin "5") (pinfunction "~{RESET}_5") (pintype "input"))
    )
    (net (code "105") (name "unconnected-(XBee-~{RTS}{slash}DIO6-Pad16)") (class "Default")
      (node (ref "XBee") (pin "16") (pinfunction "~{RTS}/DIO6_16") (pintype "bidirectional"))
    )
  )
)
